# schematic.net
KiCad netlist of a schematic drawn in EAGLE
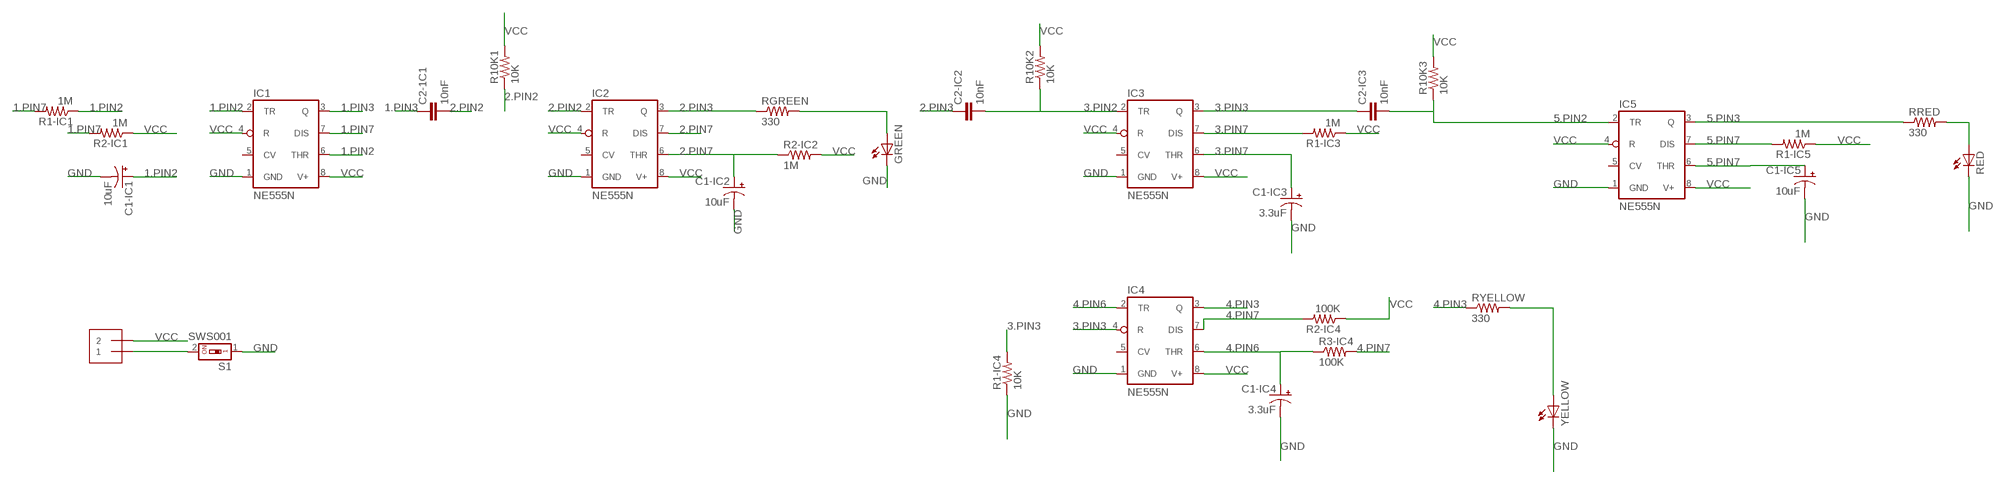
[diagram p0: schematic, sheet 1]

(export (version "E")
  (design (tool "Eeschema 10.0.6"))
  (components
    (comp (ref "C1-IC1")
      (value "10uF")
      (footprint "eagle-import:CPOL-RADIAL-2.5MM-6.5MM")
      (libsource (lib "eagle-import") (part "100UF-POLAR-RADIAL-2.5MM-25V-20%"))
    )
    (comp (ref "C1-IC2")
      (value "10uF")
      (footprint "eagle-import:CPOL-RADIAL-2.5MM-6.5MM")
      (libsource (lib "eagle-import") (part "100UF-POLAR-RADIAL-2.5MM-25V-20%"))
    )
    (comp (ref "C1-IC3")
      (value "3.3uF")
      (footprint "eagle-import:CPOL-RADIAL-2.5MM-6.5MM")
      (libsource (lib "eagle-import") (part "100UF-POLAR-RADIAL-2.5MM-25V-20%"))
    )
    (comp (ref "C1-IC4")
      (value "3.3uF")
      (footprint "eagle-import:CPOL-RADIAL-2.5MM-6.5MM")
      (libsource (lib "eagle-import") (part "100UF-POLAR-RADIAL-2.5MM-25V-20%"))
    )
    (comp (ref "C1-IC5")
      (value "10uF")
      (footprint "eagle-import:CPOL-RADIAL-2.5MM-6.5MM")
      (libsource (lib "eagle-import") (part "100UF-POLAR-RADIAL-2.5MM-25V-20%"))
    )
    (comp (ref "C2-1C1")
      (value "10nF")
      (footprint "eagle-import:0603")
      (libsource (lib "eagle-import") (part "10NF-0603-50V-10%"))
    )
    (comp (ref "C2-IC2")
      (value "10nF")
      (footprint "eagle-import:0603")
      (libsource (lib "eagle-import") (part "10NF-0603-50V-10%"))
    )
    (comp (ref "C2-IC3")
      (value "10nF")
      (footprint "eagle-import:0603")
      (libsource (lib "eagle-import") (part "10NF-0603-50V-10%"))
    )
    (comp (ref "GREEN")
      (value "LED5MM")
      (footprint "eagle-import:LED5MM")
      (libsource (lib "eagle-import") (part "LED5MM"))
    )
    (comp (ref "IC1")
      (value "NE555N")
      (footprint "eagle-import:DIL08-ROUND")
      (libsource (lib "eagle-import") (part "555NNE"))
    )
    (comp (ref "IC2")
      (value "NE555N")
      (footprint "eagle-import:DIL08-ROUND")
      (libsource (lib "eagle-import") (part "555NNE"))
    )
    (comp (ref "IC3")
      (value "NE555N")
      (footprint "eagle-import:DIL08-ROUND")
      (libsource (lib "eagle-import") (part "555NNE"))
    )
    (comp (ref "IC4")
      (value "NE555N")
      (footprint "eagle-import:DIL08-ROUND")
      (libsource (lib "eagle-import") (part "555NNE"))
    )
    (comp (ref "IC5")
      (value "NE555N")
      (footprint "eagle-import:DIL08-ROUND")
      (libsource (lib "eagle-import") (part "555NNE"))
    )
    (comp (ref "J1")
      (value "1X2-3.5MM")
      (footprint "eagle-import:1X2-3.5MM")
      (libsource (lib "eagle-import") (part "1X2-3.5MM"))
    )
    (comp (ref "R1-IC1")
      (value "1M")
      (footprint "eagle-import:0204_7")
      (libsource (lib "eagle-import") (part "R-US_0204/7"))
    )
    (comp (ref "R1-IC3")
      (value "1M")
      (footprint "eagle-import:0204_7")
      (libsource (lib "eagle-import") (part "R-US_0204/7"))
    )
    (comp (ref "R1-IC4")
      (value "10K")
      (footprint "eagle-import:0204_7")
      (libsource (lib "eagle-import") (part "R-US_0204/7"))
    )
    (comp (ref "R1-IC5")
      (value "1M")
      (footprint "eagle-import:0204_7")
      (libsource (lib "eagle-import") (part "R-US_0204/7"))
    )
    (comp (ref "R2-IC1")
      (value "1M")
      (footprint "eagle-import:0204_7")
      (libsource (lib "eagle-import") (part "R-US_0204/7"))
    )
    (comp (ref "R2-IC2")
      (value "1M")
      (footprint "eagle-import:0204_7")
      (libsource (lib "eagle-import") (part "R-US_0204/7"))
    )
    (comp (ref "R2-IC4")
      (value "100K")
      (footprint "eagle-import:0204_7")
      (libsource (lib "eagle-import") (part "R-US_0204/7"))
    )
    (comp (ref "R3-IC4")
      (value "100K")
      (footprint "eagle-import:0204_7")
      (libsource (lib "eagle-import") (part "R-US_0204/7"))
    )
    (comp (ref "R10K1")
      (value "10K")
      (footprint "eagle-import:0204_7")
      (libsource (lib "eagle-import") (part "R-US_0204/7"))
    )
    (comp (ref "R10K2")
      (value "10K")
      (footprint "eagle-import:0204_7")
      (libsource (lib "eagle-import") (part "R-US_0204/7"))
    )
    (comp (ref "R10K3")
      (value "10K")
      (footprint "eagle-import:0204_7")
      (libsource (lib "eagle-import") (part "R-US_0204/7"))
    )
    (comp (ref "RED")
      (value "LED5MM")
      (footprint "eagle-import:LED5MM")
      (libsource (lib "eagle-import") (part "LED5MM"))
    )
    (comp (ref "RGREEN")
      (value "330")
      (footprint "eagle-import:0204_7")
      (libsource (lib "eagle-import") (part "R-US_0204/7"))
    )
    (comp (ref "RRED")
      (value "330")
      (footprint "eagle-import:0204_7")
      (libsource (lib "eagle-import") (part "R-US_0204/7"))
    )
    (comp (ref "RYELLOW")
      (value "330")
      (footprint "eagle-import:0204_7")
      (libsource (lib "eagle-import") (part "R-US_0204/7"))
    )
    (comp (ref "S1")
      (value "SWS001")
      (footprint "eagle-import:SMS-001")
      (libsource (lib "eagle-import") (part "SWS001"))
    )
    (comp (ref "YELLOW")
      (value "LED5MM")
      (footprint "eagle-import:LED5MM")
      (libsource (lib "eagle-import") (part "LED5MM"))
    )
  )
  (nets
    (net (code "1") (name "/1.PIN2") (class "Default")
      (node (ref "C1-IC1") (pin "1") (pinfunction "+_1") (pintype "passive"))
      (node (ref "IC1") (pin "2") (pinfunction "TR_2") (pintype "input"))
      (node (ref "IC1") (pin "6") (pinfunction "THR_6") (pintype "input"))
      (node (ref "R1-IC1") (pin "1") (pinfunction "1_1") (pintype "passive"))
    )
    (net (code "2") (name "/1.PIN3") (class "Default")
      (node (ref "C2-1C1") (pin "1") (pinfunction "1_1") (pintype "passive"))
      (node (ref "IC1") (pin "3") (pinfunction "Q_3") (pintype "output"))
    )
    (net (code "3") (name "/1.PIN7") (class "Default")
      (node (ref "IC1") (pin "7") (pinfunction "DIS_7") (pintype "input"))
      (node (ref "R1-IC1") (pin "2") (pinfunction "2_2") (pintype "passive"))
      (node (ref "R2-IC1") (pin "2") (pinfunction "2_2") (pintype "passive"))
    )
    (net (code "4") (name "/2.PIN2") (class "Default")
      (node (ref "C2-1C1") (pin "2") (pinfunction "2_2") (pintype "passive"))
      (node (ref "IC2") (pin "2") (pinfunction "TR_2") (pintype "input"))
      (node (ref "R10K1") (pin "1") (pinfunction "1_1") (pintype "passive"))
    )
    (net (code "5") (name "/2.PIN3") (class "Default")
      (node (ref "C2-IC2") (pin "1") (pinfunction "1_1") (pintype "passive"))
      (node (ref "IC2") (pin "3") (pinfunction "Q_3") (pintype "output"))
      (node (ref "RGREEN") (pin "1") (pinfunction "1_1") (pintype "passive"))
    )
    (net (code "6") (name "/2.PIN7") (class "Default")
      (node (ref "C1-IC2") (pin "1") (pinfunction "+_1") (pintype "passive"))
      (node (ref "IC2") (pin "6") (pinfunction "THR_6") (pintype "input"))
      (node (ref "IC2") (pin "7") (pinfunction "DIS_7") (pintype "input"))
      (node (ref "R2-IC2") (pin "1") (pinfunction "1_1") (pintype "passive"))
    )
    (net (code "7") (name "/3.PIN2") (class "Default")
      (node (ref "C2-IC2") (pin "2") (pinfunction "2_2") (pintype "passive"))
      (node (ref "IC3") (pin "2") (pinfunction "TR_2") (pintype "input"))
      (node (ref "R10K2") (pin "1") (pinfunction "1_1") (pintype "passive"))
    )
    (net (code "8") (name "/3.PIN3") (class "Default")
      (node (ref "C2-IC3") (pin "1") (pinfunction "1_1") (pintype "passive"))
      (node (ref "IC3") (pin "3") (pinfunction "Q_3") (pintype "output"))
      (node (ref "IC4") (pin "4") (pinfunction "R_4") (pintype "input"))
      (node (ref "R1-IC4") (pin "2") (pinfunction "2_2") (pintype "passive"))
    )
    (net (code "9") (name "/3.PIN7") (class "Default")
      (node (ref "C1-IC3") (pin "1") (pinfunction "+_1") (pintype "passive"))
      (node (ref "IC3") (pin "6") (pinfunction "THR_6") (pintype "input"))
      (node (ref "IC3") (pin "7") (pinfunction "DIS_7") (pintype "input"))
      (node (ref "R1-IC3") (pin "2") (pinfunction "2_2") (pintype "passive"))
    )
    (net (code "10") (name "/4.PIN3") (class "Default")
      (node (ref "IC4") (pin "3") (pinfunction "Q_3") (pintype "output"))
      (node (ref "RYELLOW") (pin "1") (pinfunction "1_1") (pintype "passive"))
    )
    (net (code "11") (name "/4.PIN6") (class "Default")
      (node (ref "C1-IC4") (pin "1") (pinfunction "+_1") (pintype "passive"))
      (node (ref "IC4") (pin "2") (pinfunction "TR_2") (pintype "input"))
      (node (ref "IC4") (pin "6") (pinfunction "THR_6") (pintype "input"))
      (node (ref "R3-IC4") (pin "1") (pinfunction "1_1") (pintype "passive"))
    )
    (net (code "12") (name "/4.PIN7") (class "Default")
      (node (ref "IC4") (pin "7") (pinfunction "DIS_7") (pintype "input"))
      (node (ref "R2-IC4") (pin "2") (pinfunction "2_2") (pintype "passive"))
      (node (ref "R3-IC4") (pin "2") (pinfunction "2_2") (pintype "passive"))
    )
    (net (code "13") (name "/5.PIN2") (class "Default")
      (node (ref "C2-IC3") (pin "2") (pinfunction "2_2") (pintype "passive"))
      (node (ref "IC5") (pin "2") (pinfunction "TR_2") (pintype "input"))
      (node (ref "R10K3") (pin "1") (pinfunction "1_1") (pintype "passive"))
    )
    (net (code "14") (name "/5.PIN3") (class "Default")
      (node (ref "IC5") (pin "3") (pinfunction "Q_3") (pintype "output"))
      (node (ref "RRED") (pin "1") (pinfunction "1_1") (pintype "passive"))
    )
    (net (code "15") (name "/5.PIN7") (class "Default")
      (node (ref "C1-IC5") (pin "1") (pinfunction "+_1") (pintype "passive"))
      (node (ref "IC5") (pin "6") (pinfunction "THR_6") (pintype "input"))
      (node (ref "IC5") (pin "7") (pinfunction "DIS_7") (pintype "input"))
      (node (ref "R1-IC5") (pin "2") (pinfunction "2_2") (pintype "passive"))
    )
    (net (code "16") (name "/GND") (class "Default")
      (node (ref "C1-IC1") (pin "2") (pinfunction "-_2") (pintype "passive"))
      (node (ref "C1-IC2") (pin "2") (pinfunction "-_2") (pintype "passive"))
      (node (ref "C1-IC3") (pin "2") (pinfunction "-_2") (pintype "passive"))
      (node (ref "C1-IC4") (pin "2") (pinfunction "-_2") (pintype "passive"))
      (node (ref "C1-IC5") (pin "2") (pinfunction "-_2") (pintype "passive"))
      (node (ref "GREEN") (pin "K") (pinfunction "C_K") (pintype "passive"))
      (node (ref "IC1") (pin "1") (pinfunction "GND_1") (pintype "power_in"))
      (node (ref "IC2") (pin "1") (pinfunction "GND_1") (pintype "power_in"))
      (node (ref "IC3") (pin "1") (pinfunction "GND_1") (pintype "power_in"))
      (node (ref "IC4") (pin "1") (pinfunction "GND_1") (pintype "power_in"))
      (node (ref "IC5") (pin "1") (pinfunction "GND_1") (pintype "power_in"))
      (node (ref "R1-IC4") (pin "1") (pinfunction "1_1") (pintype "passive"))
      (node (ref "RED") (pin "K") (pinfunction "C_K") (pintype "passive"))
      (node (ref "S1") (pin "1") (pinfunction "1_1") (pintype "passive"))
      (node (ref "YELLOW") (pin "K") (pinfunction "C_K") (pintype "passive"))
    )
    (net (code "17") (name "/VCC") (class "Default")
      (node (ref "IC1") (pin "4") (pinfunction "R_4") (pintype "input"))
      (node (ref "IC1") (pin "8") (pinfunction "V+_8") (pintype "power_in"))
      (node (ref "IC2") (pin "4") (pinfunction "R_4") (pintype "input"))
      (node (ref "IC2") (pin "8") (pinfunction "V+_8") (pintype "power_in"))
      (node (ref "IC3") (pin "4") (pinfunction "R_4") (pintype "input"))
      (node (ref "IC3") (pin "8") (pinfunction "V+_8") (pintype "power_in"))
      (node (ref "IC4") (pin "8") (pinfunction "V+_8") (pintype "power_in"))
      (node (ref "IC5") (pin "4") (pinfunction "R_4") (pintype "input"))
      (node (ref "IC5") (pin "8") (pinfunction "V+_8") (pintype "power_in"))
      (node (ref "J1") (pin "2") (pinfunction "2_2") (pintype "passive"))
      (node (ref "R1-IC3") (pin "1") (pinfunction "1_1") (pintype "passive"))
      (node (ref "R1-IC5") (pin "1") (pinfunction "1_1") (pintype "passive"))
      (node (ref "R10K1") (pin "2") (pinfunction "2_2") (pintype "passive"))
      (node (ref "R10K2") (pin "2") (pinfunction "2_2") (pintype "passive"))
      (node (ref "R10K3") (pin "2") (pinfunction "2_2") (pintype "passive"))
      (node (ref "R2-IC1") (pin "1") (pinfunction "1_1") (pintype "passive"))
      (node (ref "R2-IC2") (pin "2") (pinfunction "2_2") (pintype "passive"))
      (node (ref "R2-IC4") (pin "1") (pinfunction "1_1") (pintype "passive"))
    )
    (net (code "18") (name "Net-(GREEN-PadA)") (class "Default")
      (node (ref "GREEN") (pin "A") (pinfunction "A_A") (pintype "passive"))
      (node (ref "RGREEN") (pin "2") (pinfunction "2_2") (pintype "passive"))
    )
    (net (code "19") (name "Net-(J1-Pad1)") (class "Default")
      (node (ref "J1") (pin "1") (pinfunction "1_1") (pintype "passive"))
      (node (ref "S1") (pin "2") (pinfunction "2_2") (pintype "passive"))
    )
    (net (code "20") (name "Net-(RED-PadA)") (class "Default")
      (node (ref "RED") (pin "A") (pinfunction "A_A") (pintype "passive"))
      (node (ref "RRED") (pin "2") (pinfunction "2_2") (pintype "passive"))
    )
    (net (code "21") (name "Net-(RYELLOW-Pad2)") (class "Default")
      (node (ref "RYELLOW") (pin "2") (pinfunction "2_2") (pintype "passive"))
      (node (ref "YELLOW") (pin "A") (pinfunction "A_A") (pintype "passive"))
    )
    (net (code "22") (name "unconnected-(IC1-CV-Pad5)") (class "Default")
      (node (ref "IC1") (pin "5") (pinfunction "CV_5") (pintype "input"))
    )
    (net (code "23") (name "unconnected-(IC2-CV-Pad5)") (class "Default")
      (node (ref "IC2") (pin "5") (pinfunction "CV_5") (pintype "input"))
    )
    (net (code "24") (name "unconnected-(IC3-CV-Pad5)") (class "Default")
      (node (ref "IC3") (pin "5") (pinfunction "CV_5") (pintype "input"))
    )
    (net (code "25") (name "unconnected-(IC4-CV-Pad5)") (class "Default")
      (node (ref "IC4") (pin "5") (pinfunction "CV_5") (pintype "input"))
    )
    (net (code "26") (name "unconnected-(IC5-CV-Pad5)") (class "Default")
      (node (ref "IC5") (pin "5") (pinfunction "CV_5") (pintype "input"))
    )
  )
)
